# HTVC_connector_board.net
KiCad netlist of a schematic drawn in EAGLE
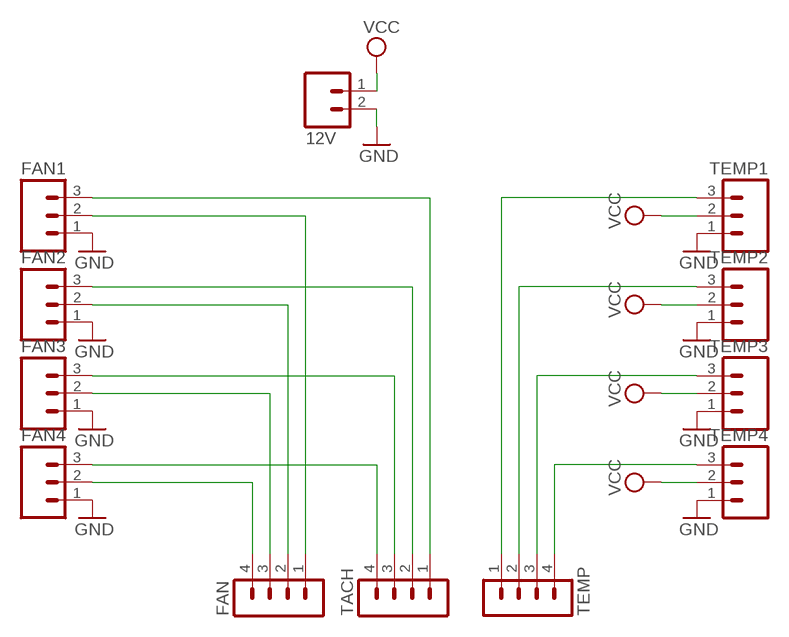
[diagram p0: schematic, sheet 1]

(export (version "E")
  (design (tool "Eeschema 10.0.6"))
  (components
    (comp (ref "12V")
      (value "M02PTH")
      (footprint "eagle-import:1X02")
      (libsource (lib "eagle-import") (part "M02PTH"))
    )
    (comp (ref "FAN")
      (value "MA04-1")
      (footprint "eagle-import:MA04-1")
      (libsource (lib "eagle-import") (part "MA04-1"))
    )
    (comp (ref "FAN1")
      (value "M03POLAR")
      (footprint "eagle-import:MOLEX-1X3")
      (libsource (lib "eagle-import") (part "M03POLAR"))
    )
    (comp (ref "FAN2")
      (value "M03POLAR")
      (footprint "eagle-import:MOLEX-1X3")
      (libsource (lib "eagle-import") (part "M03POLAR"))
    )
    (comp (ref "FAN3")
      (value "M03POLAR")
      (footprint "eagle-import:MOLEX-1X3")
      (libsource (lib "eagle-import") (part "M03POLAR"))
    )
    (comp (ref "FAN4")
      (value "M03POLAR")
      (footprint "eagle-import:MOLEX-1X3")
      (libsource (lib "eagle-import") (part "M03POLAR"))
    )
    (comp (ref "TACH")
      (value "MA04-1")
      (footprint "eagle-import:MA04-1")
      (libsource (lib "eagle-import") (part "MA04-1"))
    )
    (comp (ref "TEMP")
      (value "MA04-1")
      (footprint "eagle-import:MA04-1")
      (libsource (lib "eagle-import") (part "MA04-1"))
    )
    (comp (ref "TEMP1")
      (value "M03POLAR")
      (footprint "eagle-import:MOLEX-1X3")
      (libsource (lib "eagle-import") (part "M03POLAR"))
    )
    (comp (ref "TEMP2")
      (value "M03POLAR")
      (footprint "eagle-import:MOLEX-1X3")
      (libsource (lib "eagle-import") (part "M03POLAR"))
    )
    (comp (ref "TEMP3")
      (value "M03POLAR")
      (footprint "eagle-import:MOLEX-1X3")
      (libsource (lib "eagle-import") (part "M03POLAR"))
    )
    (comp (ref "TEMP4")
      (value "M03POLAR")
      (footprint "eagle-import:MOLEX-1X3")
      (libsource (lib "eagle-import") (part "M03POLAR"))
    )
  )
  (nets
    (net (code "1") (name "GND") (class "Default")
      (node (ref "12V") (pin "2") (pinfunction "2_2") (pintype "passive"))
      (node (ref "FAN1") (pin "1") (pinfunction "1_1") (pintype "passive"))
      (node (ref "FAN2") (pin "1") (pinfunction "1_1") (pintype "passive"))
      (node (ref "FAN3") (pin "1") (pinfunction "1_1") (pintype "passive"))
      (node (ref "FAN4") (pin "1") (pinfunction "1_1") (pintype "passive"))
      (node (ref "TEMP1") (pin "1") (pinfunction "1_1") (pintype "passive"))
      (node (ref "TEMP2") (pin "1") (pinfunction "1_1") (pintype "passive"))
      (node (ref "TEMP3") (pin "1") (pinfunction "1_1") (pintype "passive"))
      (node (ref "TEMP4") (pin "1") (pinfunction "1_1") (pintype "passive"))
    )
    (net (code "2") (name "Net-(FAN-Pad1)") (class "Default")
      (node (ref "FAN") (pin "1") (pinfunction "1_1") (pintype "passive"))
      (node (ref "FAN1") (pin "2") (pinfunction "2_2") (pintype "passive"))
    )
    (net (code "3") (name "Net-(FAN-Pad2)") (class "Default")
      (node (ref "FAN") (pin "2") (pinfunction "2_2") (pintype "passive"))
      (node (ref "FAN2") (pin "2") (pinfunction "2_2") (pintype "passive"))
    )
    (net (code "4") (name "Net-(FAN-Pad3)") (class "Default")
      (node (ref "FAN") (pin "3") (pinfunction "3_3") (pintype "passive"))
      (node (ref "FAN3") (pin "2") (pinfunction "2_2") (pintype "passive"))
    )
    (net (code "5") (name "Net-(FAN-Pad4)") (class "Default")
      (node (ref "FAN") (pin "4") (pinfunction "4_4") (pintype "passive"))
      (node (ref "FAN4") (pin "2") (pinfunction "2_2") (pintype "passive"))
    )
    (net (code "6") (name "Net-(FAN1-Pad3)") (class "Default")
      (node (ref "FAN1") (pin "3") (pinfunction "3_3") (pintype "passive"))
      (node (ref "TACH") (pin "1") (pinfunction "1_1") (pintype "passive"))
    )
    (net (code "7") (name "Net-(FAN2-Pad3)") (class "Default")
      (node (ref "FAN2") (pin "3") (pinfunction "3_3") (pintype "passive"))
      (node (ref "TACH") (pin "2") (pinfunction "2_2") (pintype "passive"))
    )
    (net (code "8") (name "Net-(FAN3-Pad3)") (class "Default")
      (node (ref "FAN3") (pin "3") (pinfunction "3_3") (pintype "passive"))
      (node (ref "TACH") (pin "3") (pinfunction "3_3") (pintype "passive"))
    )
    (net (code "9") (name "Net-(FAN4-Pad3)") (class "Default")
      (node (ref "FAN4") (pin "3") (pinfunction "3_3") (pintype "passive"))
      (node (ref "TACH") (pin "4") (pinfunction "4_4") (pintype "passive"))
    )
    (net (code "10") (name "Net-(TEMP-Pad1)") (class "Default")
      (node (ref "TEMP") (pin "1") (pinfunction "1_1") (pintype "passive"))
      (node (ref "TEMP1") (pin "3") (pinfunction "3_3") (pintype "passive"))
    )
    (net (code "11") (name "Net-(TEMP-Pad2)") (class "Default")
      (node (ref "TEMP") (pin "2") (pinfunction "2_2") (pintype "passive"))
      (node (ref "TEMP2") (pin "3") (pinfunction "3_3") (pintype "passive"))
    )
    (net (code "12") (name "Net-(TEMP-Pad3)") (class "Default")
      (node (ref "TEMP") (pin "3") (pinfunction "3_3") (pintype "passive"))
      (node (ref "TEMP3") (pin "3") (pinfunction "3_3") (pintype "passive"))
    )
    (net (code "13") (name "Net-(TEMP-Pad4)") (class "Default")
      (node (ref "TEMP") (pin "4") (pinfunction "4_4") (pintype "passive"))
      (node (ref "TEMP4") (pin "3") (pinfunction "3_3") (pintype "passive"))
    )
    (net (code "14") (name "VCC") (class "Default")
      (node (ref "12V") (pin "1") (pinfunction "1_1") (pintype "passive"))
      (node (ref "TEMP1") (pin "2") (pinfunction "2_2") (pintype "passive"))
      (node (ref "TEMP2") (pin "2") (pinfunction "2_2") (pintype "passive"))
      (node (ref "TEMP3") (pin "2") (pinfunction "2_2") (pintype "passive"))
      (node (ref "TEMP4") (pin "2") (pinfunction "2_2") (pintype "passive"))
    )
  )
)
